# Control_PCb.net
KiCad netlist of a schematic drawn in EAGLE
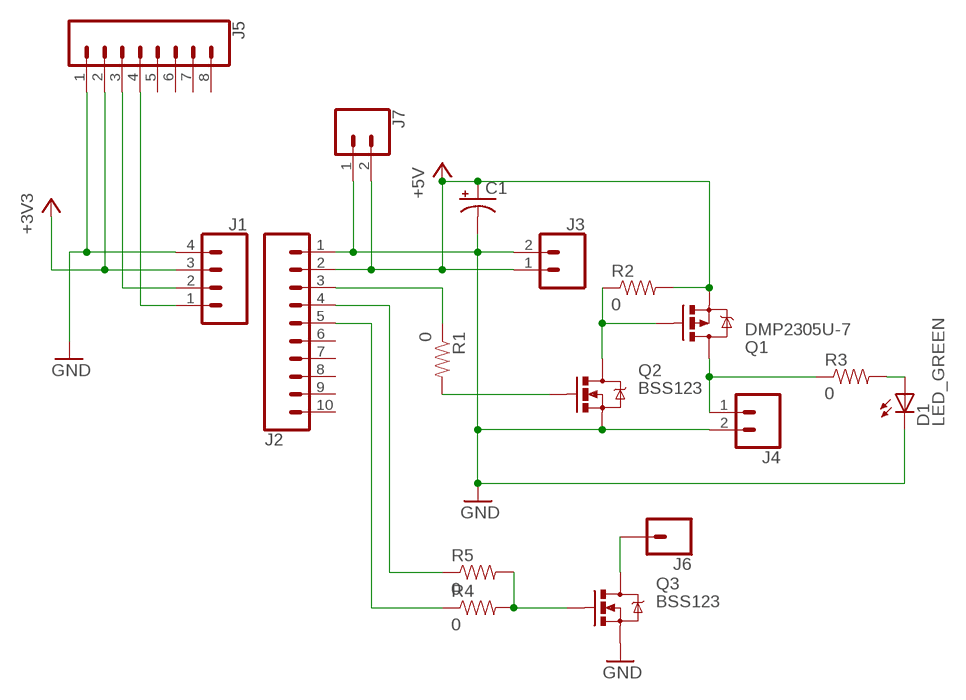
[diagram p0: schematic, sheet 1]

(export (version "E")
  (design (tool "Eeschema 10.0.6"))
  (components
    (comp (ref "C1")
      (value "CPOL-USE2,5-6E")
      (footprint "eagle-import:E2,5-6E")
      (libsource (lib "eagle-import") (part "CPOL-USE2,5-6E"))
    )
    (comp (ref "D1")
      (value "LED_GREEN")
      (footprint "eagle-import:CHIP_LED0805")
      (fields (field (name "PARTNO") "LTST-S220GKT"))
      (libsource (lib "eagle-import") (part "LED_GREEN"))
    )
    (comp (ref "J1")
      (value "CONN_04LOCK_LONGPADS")
      (footprint "eagle-import:1X04_LOCK_LONGPADS")
      (libsource (lib "eagle-import") (part "CONN_04LOCK_LONGPADS"))
    )
    (comp (ref "J2")
      (value "CONN_10LOCK_LONGPADS")
      (footprint "eagle-import:1X10_LOCK_LONGPADS")
      (libsource (lib "eagle-import") (part "CONN_10LOCK_LONGPADS"))
    )
    (comp (ref "J3")
      (value "CONN_023.5MM")
      (footprint "eagle-import:SCREWTERMINAL-3.5MM-2")
      (libsource (lib "eagle-import") (part "CONN_023.5MM"))
    )
    (comp (ref "J4")
      (value "CONN_023.5MM")
      (footprint "eagle-import:SCREWTERMINAL-3.5MM-2")
      (libsource (lib "eagle-import") (part "CONN_023.5MM"))
    )
    (comp (ref "J5")
      (value "CONN_08LOCK_LONGPADS")
      (footprint "eagle-import:1X08_LOCK_LONGPADS")
      (libsource (lib "eagle-import") (part "CONN_08LOCK_LONGPADS"))
    )
    (comp (ref "J6")
      (value "CONN_01OFFSET")
      (footprint "eagle-import:1X01_OFFSET")
      (libsource (lib "eagle-import") (part "CONN_01OFFSET"))
    )
    (comp (ref "J7")
      (value "CONN_02LOCK_LONGPADS")
      (footprint "eagle-import:1X02_LOCK_LONGPADS")
      (libsource (lib "eagle-import") (part "CONN_02LOCK_LONGPADS"))
    )
    (comp (ref "Q1")
      (value "DMP2305U-7")
      (footprint "eagle-import:SOT23")
      (libsource (lib "eagle-import") (part "MOS-P_DMP2305U-7"))
    )
    (comp (ref "Q2")
      (value "BSS123")
      (footprint "eagle-import:SOT23")
      (fields (field (name "PARTNO") "BSS123,215"))
      (libsource (lib "eagle-import") (part "MOS-N_BSS123"))
    )
    (comp (ref "Q3")
      (value "BSS123")
      (footprint "eagle-import:SOT23")
      (fields (field (name "PARTNO") "BSS123,215"))
      (libsource (lib "eagle-import") (part "MOS-N_BSS123"))
    )
    (comp (ref "R1")
      (value "0")
      (footprint "eagle-import:0805")
      (fields (field (name "PARTNO") "RC0805JR-070RL"))
      (libsource (lib "eagle-import") (part "RES_0_0805"))
    )
    (comp (ref "R2")
      (value "0")
      (footprint "eagle-import:0805")
      (fields (field (name "PARTNO") "RC0805JR-070RL"))
      (libsource (lib "eagle-import") (part "RES_0_0805"))
    )
    (comp (ref "R3")
      (value "0")
      (footprint "eagle-import:0805")
      (fields (field (name "PARTNO") "RC0805JR-070RL"))
      (libsource (lib "eagle-import") (part "RES_0_0805"))
    )
    (comp (ref "R4")
      (value "0")
      (footprint "eagle-import:0805")
      (fields (field (name "PARTNO") "RC0805JR-070RL"))
      (libsource (lib "eagle-import") (part "RES_0_0805"))
    )
    (comp (ref "R5")
      (value "0")
      (footprint "eagle-import:0805")
      (fields (field (name "PARTNO") "RC0805JR-070RL"))
      (libsource (lib "eagle-import") (part "RES_0_0805"))
    )
  )
  (nets
    (net (code "1") (name "+3V3") (class "Default")
      (node (ref "J1") (pin "3") (pinfunction "3_3") (pintype "passive"))
      (node (ref "J5") (pin "2") (pinfunction "2_2") (pintype "passive"))
    )
    (net (code "2") (name "+5V") (class "Default")
      (node (ref "C1") (pin "+") (pinfunction "+_+") (pintype "passive"))
      (node (ref "J2") (pin "2") (pinfunction "2_2") (pintype "passive"))
      (node (ref "J3") (pin "1") (pinfunction "1_1") (pintype "passive"))
      (node (ref "J7") (pin "2") (pinfunction "2_2") (pintype "passive"))
      (node (ref "Q1") (pin "3") (pinfunction "S_3") (pintype "passive"))
      (node (ref "R2") (pin "2") (pinfunction "2_2") (pintype "passive"))
    )
    (net (code "3") (name "GND") (class "Default")
      (node (ref "C1") (pin "-") (pinfunction "-_-") (pintype "passive"))
      (node (ref "D1") (pin "C") (pinfunction "C_C") (pintype "passive"))
      (node (ref "J1") (pin "4") (pinfunction "4_4") (pintype "passive"))
      (node (ref "J2") (pin "1") (pinfunction "1_1") (pintype "passive"))
      (node (ref "J3") (pin "2") (pinfunction "2_2") (pintype "passive"))
      (node (ref "J4") (pin "2") (pinfunction "2_2") (pintype "passive"))
      (node (ref "J5") (pin "1") (pinfunction "1_1") (pintype "passive"))
      (node (ref "J7") (pin "1") (pinfunction "1_1") (pintype "passive"))
      (node (ref "Q2") (pin "2") (pinfunction "S_2") (pintype "passive"))
      (node (ref "Q3") (pin "2") (pinfunction "S_2") (pintype "passive"))
    )
    (net (code "4") (name "Net-(D1-PadA)") (class "Default")
      (node (ref "D1") (pin "A") (pinfunction "A_A") (pintype "passive"))
      (node (ref "R3") (pin "2") (pinfunction "2_2") (pintype "passive"))
    )
    (net (code "5") (name "Net-(J1-Pad1)") (class "Default")
      (node (ref "J1") (pin "1") (pinfunction "1_1") (pintype "passive"))
      (node (ref "J5") (pin "4") (pinfunction "4_4") (pintype "passive"))
    )
    (net (code "6") (name "Net-(J1-Pad2)") (class "Default")
      (node (ref "J1") (pin "2") (pinfunction "2_2") (pintype "passive"))
      (node (ref "J5") (pin "3") (pinfunction "3_3") (pintype "passive"))
    )
    (net (code "7") (name "Net-(J2-Pad3)") (class "Default")
      (node (ref "J2") (pin "3") (pinfunction "3_3") (pintype "passive"))
      (node (ref "R1") (pin "1") (pinfunction "1_1") (pintype "passive"))
    )
    (net (code "8") (name "Net-(J2-Pad4)") (class "Default")
      (node (ref "J2") (pin "4") (pinfunction "4_4") (pintype "passive"))
      (node (ref "R5") (pin "1") (pinfunction "1_1") (pintype "passive"))
    )
    (net (code "9") (name "Net-(J2-Pad5)") (class "Default")
      (node (ref "J2") (pin "5") (pinfunction "5_5") (pintype "passive"))
      (node (ref "R4") (pin "1") (pinfunction "1_1") (pintype "passive"))
    )
    (net (code "10") (name "Net-(Q1-D)") (class "Default")
      (node (ref "J4") (pin "1") (pinfunction "1_1") (pintype "passive"))
      (node (ref "Q1") (pin "2") (pinfunction "D_2") (pintype "passive"))
      (node (ref "R3") (pin "1") (pinfunction "1_1") (pintype "passive"))
    )
    (net (code "11") (name "Net-(Q1-G)") (class "Default")
      (node (ref "Q1") (pin "1") (pinfunction "G_1") (pintype "passive"))
      (node (ref "Q2") (pin "3") (pinfunction "D_3") (pintype "passive"))
      (node (ref "R2") (pin "1") (pinfunction "1_1") (pintype "passive"))
    )
    (net (code "12") (name "Net-(Q2-G)") (class "Default")
      (node (ref "Q2") (pin "1") (pinfunction "G_1") (pintype "passive"))
      (node (ref "R1") (pin "2") (pinfunction "2_2") (pintype "passive"))
    )
    (net (code "13") (name "Net-(Q3-D)") (class "Default")
      (node (ref "J6") (pin "1") (pinfunction "1_1") (pintype "passive"))
      (node (ref "Q3") (pin "3") (pinfunction "D_3") (pintype "passive"))
    )
    (net (code "14") (name "Net-(Q3-G)") (class "Default")
      (node (ref "Q3") (pin "1") (pinfunction "G_1") (pintype "passive"))
      (node (ref "R4") (pin "2") (pinfunction "2_2") (pintype "passive"))
      (node (ref "R5") (pin "2") (pinfunction "2_2") (pintype "passive"))
    )
    (net (code "15") (name "unconnected-(J2-Pad6)") (class "Default")
      (node (ref "J2") (pin "6") (pinfunction "6_6") (pintype "passive"))
    )
    (net (code "16") (name "unconnected-(J2-Pad7)") (class "Default")
      (node (ref "J2") (pin "7") (pinfunction "7_7") (pintype "passive"))
    )
    (net (code "17") (name "unconnected-(J2-Pad8)") (class "Default")
      (node (ref "J2") (pin "8") (pinfunction "8_8") (pintype "passive"))
    )
    (net (code "18") (name "unconnected-(J2-Pad9)") (class "Default")
      (node (ref "J2") (pin "9") (pinfunction "9_9") (pintype "passive"))
    )
    (net (code "19") (name "unconnected-(J2-Pad10)") (class "Default")
      (node (ref "J2") (pin "10") (pinfunction "10_10") (pintype "passive"))
    )
    (net (code "20") (name "unconnected-(J5-Pad5)") (class "Default")
      (node (ref "J5") (pin "5") (pinfunction "5_5") (pintype "passive"))
    )
    (net (code "21") (name "unconnected-(J5-Pad6)") (class "Default")
      (node (ref "J5") (pin "6") (pinfunction "6_6") (pintype "passive"))
    )
    (net (code "22") (name "unconnected-(J5-Pad7)") (class "Default")
      (node (ref "J5") (pin "7") (pinfunction "7_7") (pintype "passive"))
    )
    (net (code "23") (name "unconnected-(J5-Pad8)") (class "Default")
      (node (ref "J5") (pin "8") (pinfunction "8_8") (pintype "passive"))
    )
  )
)
